# arduino_board_rev_1_3.net
KiCad netlist of a schematic drawn in EAGLE
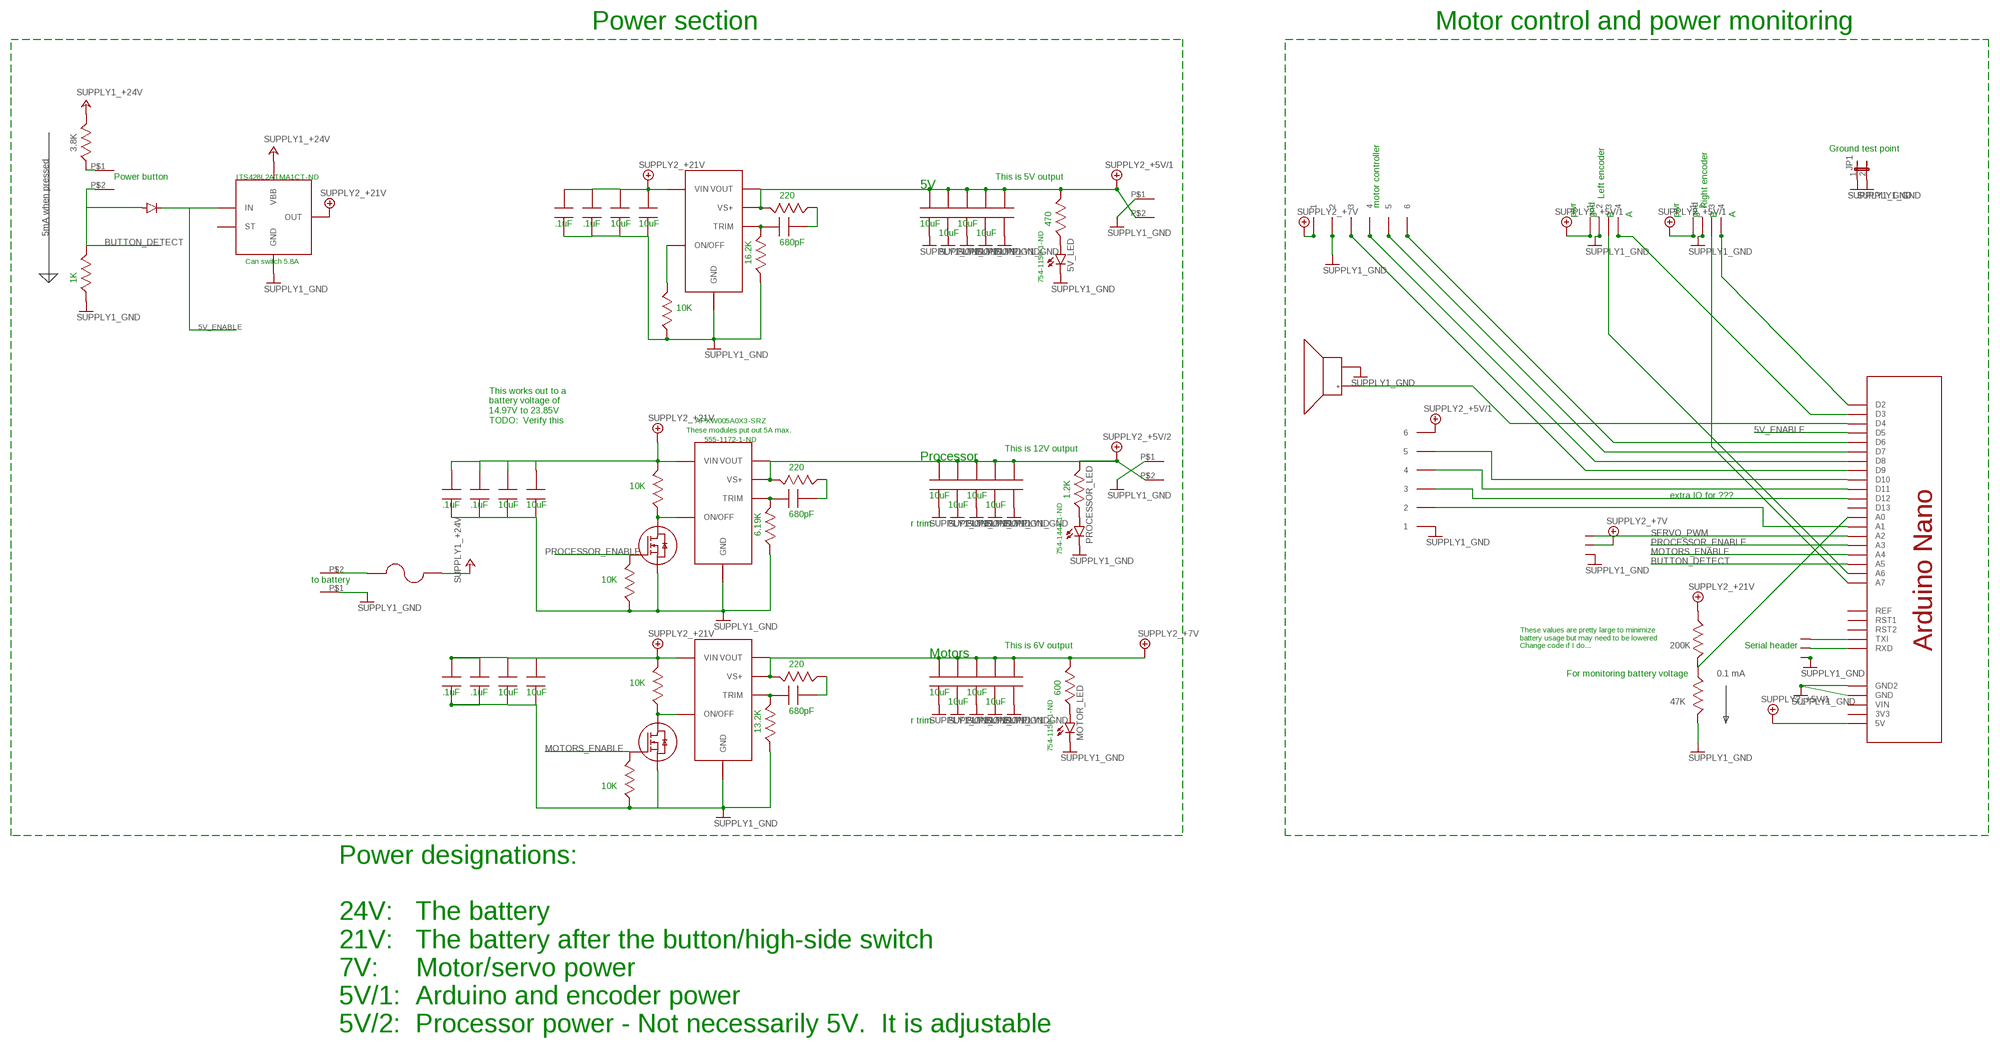
[diagram p0: schematic, sheet 1]

(export (version "E")
  (design (tool "Eeschema 10.0.6"))
  (components
    (comp (ref "5V_C_680PF")
      (value "JACK_CAPACITOR0805")
      (footprint "eagle-import:JACK_0805")
      (libsource (lib "eagle-import") (part "JACK_CAPACITOR0805"))
    )
    (comp (ref "5V_IN_CAP_1")
      (value "JACK_CAPACITOR")
      (footprint "eagle-import:JACK_1210")
      (libsource (lib "eagle-import") (part "JACK_CAPACITOR"))
    )
    (comp (ref "5V_IN_CAP_2")
      (value "JACK_CAPACITOR")
      (footprint "eagle-import:JACK_1210")
      (libsource (lib "eagle-import") (part "JACK_CAPACITOR"))
    )
    (comp (ref "5V_IN_CAP_3")
      (value "JACK_CAPACITOR")
      (footprint "eagle-import:JACK_1210")
      (libsource (lib "eagle-import") (part "JACK_CAPACITOR"))
    )
    (comp (ref "5V_IN_CAP_4")
      (value "JACK_CAPACITOR")
      (footprint "eagle-import:JACK_1210")
      (libsource (lib "eagle-import") (part "JACK_CAPACITOR"))
    )
    (comp (ref "5V_LED")
      (value "LED_LEDSML1206")
      (footprint "eagle-import:LED_SML1206")
      (libsource (lib "eagle-import") (part "LED_LEDSML1206"))
    )
    (comp (ref "5V_LED_R1")
      (value "JACK_RESISTOR0805")
      (footprint "eagle-import:JACK_0805")
      (libsource (lib "eagle-import") (part "JACK_RESISTOR0805"))
    )
    (comp (ref "5V_OUT_CAP_1")
      (value "JACK_CAPACITOR")
      (footprint "eagle-import:JACK_1210")
      (libsource (lib "eagle-import") (part "JACK_CAPACITOR"))
    )
    (comp (ref "5V_OUT_CAP_2")
      (value "JACK_CAPACITOR")
      (footprint "eagle-import:JACK_1210")
      (libsource (lib "eagle-import") (part "JACK_CAPACITOR"))
    )
    (comp (ref "5V_OUT_CAP_3")
      (value "JACK_CAPACITOR")
      (footprint "eagle-import:JACK_1210")
      (libsource (lib "eagle-import") (part "JACK_CAPACITOR"))
    )
    (comp (ref "5V_OUT_CAP_4")
      (value "JACK_CAPACITOR")
      (footprint "eagle-import:JACK_1210")
      (libsource (lib "eagle-import") (part "JACK_CAPACITOR"))
    )
    (comp (ref "5V_OUT_CAP_5")
      (value "JACK_CAPACITOR")
      (footprint "eagle-import:JACK_1210")
      (libsource (lib "eagle-import") (part "JACK_CAPACITOR"))
    )
    (comp (ref "5V_REGULATOR_PULLDOWN")
      (value "JACK_RESISTOR0805")
      (footprint "eagle-import:JACK_0805")
      (libsource (lib "eagle-import") (part "JACK_RESISTOR0805"))
    )
    (comp (ref "5V_R_220")
      (value "JACK_RESISTOR0805")
      (footprint "eagle-import:JACK_0805")
      (libsource (lib "eagle-import") (part "JACK_RESISTOR0805"))
    )
    (comp (ref "BATTERY_VOLTAGE_DIVIDER_HIGH")
      (value "JACK_RESISTOR0805")
      (footprint "eagle-import:JACK_0805")
      (libsource (lib "eagle-import") (part "JACK_RESISTOR0805"))
    )
    (comp (ref "BATTERY_VOLTAGE_DIVIDER_LOW")
      (value "JACK_RESISTOR0805")
      (footprint "eagle-import:JACK_0805")
      (libsource (lib "eagle-import") (part "JACK_RESISTOR0805"))
    )
    (comp (ref "BEEPER")
      (value "JACK_BEEPER")
      (footprint "eagle-import:JACK_BEEPER_433-1033-ND")
      (libsource (lib "eagle-import") (part "JACK_BEEPER"))
    )
    (comp (ref "DC2DC_PROCESSOR_")
      (value "JACK_DC_TO_DC_VARIABLE_555-1172-1-ND")
      (footprint "eagle-import:JACK_DC2DC_555-1172-1-ND")
      (libsource (lib "eagle-import") (part "JACK_DC_TO_DC_VARIABLE_555-1172-1-ND"))
    )
    (comp (ref "HIGH-SIDE_BLOCKING_DIODE")
      (value "JACK_DIODESOD-23/SC-76")
      (footprint "eagle-import:JACK_SOD-323_SC-76")
      (libsource (lib "eagle-import") (part "JACK_DIODESOD-23/SC-76"))
    )
    (comp (ref "HIGH-SIDE_BUTTON_DIVIDER_HIGH")
      (value "JACK_RESISTOR0805")
      (footprint "eagle-import:JACK_0805")
      (libsource (lib "eagle-import") (part "JACK_RESISTOR0805"))
    )
    (comp (ref "HIGH-SIDE_SWITCH")
      (value "JACK_HIGH-SIDE_SWITCH_INFINEON_ITS428L2")
      (footprint "eagle-import:JACK_INFINEON_TO-252-5-11")
      (libsource (lib "eagle-import") (part "JACK_HIGH-SIDE_SWITCH_INFINEON_ITS428L2"))
    )
    (comp (ref "HIGH-SIDE_SWITCH_BUTTON_DIVIDER_LOW")
      (value "JACK_RESISTOR0805")
      (footprint "eagle-import:JACK_0805")
      (libsource (lib "eagle-import") (part "JACK_RESISTOR0805"))
    )
    (comp (ref "JP1")
      (value "JUMPER_JP1E")
      (footprint "eagle-import:JUMPER_JP1")
      (libsource (lib "eagle-import") (part "JUMPER_JP1E"))
    )
    (comp (ref "MOTOR.1UF")
      (value "JACK_CAPACITOR")
      (footprint "eagle-import:JACK_1210")
      (libsource (lib "eagle-import") (part "JACK_CAPACITOR"))
    )
    (comp (ref "MOTOR_C_680PF")
      (value "JACK_CAPACITOR0805")
      (footprint "eagle-import:JACK_0805")
      (libsource (lib "eagle-import") (part "JACK_CAPACITOR0805"))
    )
    (comp (ref "MOTOR_ENABLE_MOSFET")
      (value "JACK_MOSFET_N_CHANNELBSS138LCT-ND")
      (footprint "eagle-import:JACK_SOT23")
      (libsource (lib "eagle-import") (part "JACK_MOSFET_N_CHANNELBSS138LCT-ND"))
    )
    (comp (ref "MOTOR_IN.1UF")
      (value "JACK_CAPACITOR")
      (footprint "eagle-import:JACK_1210")
      (libsource (lib "eagle-import") (part "JACK_CAPACITOR"))
    )
    (comp (ref "MOTOR_IN.1UF1")
      (value "JACK_CAPACITOR")
      (footprint "eagle-import:JACK_1210")
      (libsource (lib "eagle-import") (part "JACK_CAPACITOR"))
    )
    (comp (ref "MOTOR_IN.1UF4")
      (value "JACK_CAPACITOR")
      (footprint "eagle-import:JACK_1210")
      (libsource (lib "eagle-import") (part "JACK_CAPACITOR"))
    )
    (comp (ref "MOTOR_IN10UF")
      (value "JACK_CAPACITOR")
      (footprint "eagle-import:JACK_1210")
      (libsource (lib "eagle-import") (part "JACK_CAPACITOR"))
    )
    (comp (ref "MOTOR_LED")
      (value "LED_LEDSML1206")
      (footprint "eagle-import:LED_SML1206")
      (libsource (lib "eagle-import") (part "LED_LEDSML1206"))
    )
    (comp (ref "MOTOR_LED_R")
      (value "JACK_RESISTOR0805")
      (footprint "eagle-import:JACK_0805")
      (libsource (lib "eagle-import") (part "JACK_RESISTOR0805"))
    )
    (comp (ref "MOTOR_MOSFET_PULLDOWN")
      (value "JACK_RESISTOR0805")
      (footprint "eagle-import:JACK_0805")
      (libsource (lib "eagle-import") (part "JACK_RESISTOR0805"))
    )
    (comp (ref "MOTOR_PULLUP")
      (value "JACK_RESISTOR0805")
      (footprint "eagle-import:JACK_0805")
      (libsource (lib "eagle-import") (part "JACK_RESISTOR0805"))
    )
    (comp (ref "MOTOR_R_220")
      (value "JACK_RESISTOR0805")
      (footprint "eagle-import:JACK_0805")
      (libsource (lib "eagle-import") (part "JACK_RESISTOR0805"))
    )
    (comp (ref "MOTOR_TRIM")
      (value "JACK_RESISTOR0805")
      (footprint "eagle-import:JACK_0805")
      (libsource (lib "eagle-import") (part "JACK_RESISTOR0805"))
    )
    (comp (ref "MOTOTR10UF")
      (value "JACK_CAPACITOR")
      (footprint "eagle-import:JACK_1210")
      (libsource (lib "eagle-import") (part "JACK_CAPACITOR"))
    )
    (comp (ref "MOTOTR10UF1")
      (value "JACK_CAPACITOR")
      (footprint "eagle-import:JACK_1210")
      (libsource (lib "eagle-import") (part "JACK_CAPACITOR"))
    )
    (comp (ref "MOTOTR10UF2")
      (value "JACK_CAPACITOR")
      (footprint "eagle-import:JACK_1210")
      (libsource (lib "eagle-import") (part "JACK_CAPACITOR"))
    )
    (comp (ref "MOTOTR10UF3")
      (value "JACK_CAPACITOR")
      (footprint "eagle-import:JACK_1210")
      (libsource (lib "eagle-import") (part "JACK_CAPACITOR"))
    )
    (comp (ref "PROC.1UF")
      (value "JACK_CAPACITOR")
      (footprint "eagle-import:JACK_1210")
      (libsource (lib "eagle-import") (part "JACK_CAPACITOR"))
    )
    (comp (ref "PROC10UF")
      (value "JACK_CAPACITOR")
      (footprint "eagle-import:JACK_1210")
      (libsource (lib "eagle-import") (part "JACK_CAPACITOR"))
    )
    (comp (ref "PROC10UF1")
      (value "JACK_CAPACITOR")
      (footprint "eagle-import:JACK_1210")
      (libsource (lib "eagle-import") (part "JACK_CAPACITOR"))
    )
    (comp (ref "PROC10UF2")
      (value "JACK_CAPACITOR")
      (footprint "eagle-import:JACK_1210")
      (libsource (lib "eagle-import") (part "JACK_CAPACITOR"))
    )
    (comp (ref "PROC10UF3")
      (value "JACK_CAPACITOR")
      (footprint "eagle-import:JACK_1210")
      (libsource (lib "eagle-import") (part "JACK_CAPACITOR"))
    )
    (comp (ref "PROCESSOR_C_680PF")
      (value "JACK_CAPACITOR0805")
      (footprint "eagle-import:JACK_0805")
      (libsource (lib "eagle-import") (part "JACK_CAPACITOR0805"))
    )
    (comp (ref "PROCESSOR_ENABLE_MOSFET")
      (value "JACK_MOSFET_N_CHANNELBSS138LCT-ND")
      (footprint "eagle-import:JACK_SOT23")
      (libsource (lib "eagle-import") (part "JACK_MOSFET_N_CHANNELBSS138LCT-ND"))
    )
    (comp (ref "PROCESSOR_LED")
      (value "LED_LEDSML1206")
      (footprint "eagle-import:LED_SML1206")
      (libsource (lib "eagle-import") (part "LED_LEDSML1206"))
    )
    (comp (ref "PROCESSOR_LED_R")
      (value "JACK_RESISTOR0805")
      (footprint "eagle-import:JACK_0805")
      (libsource (lib "eagle-import") (part "JACK_RESISTOR0805"))
    )
    (comp (ref "PROCESSOR_MOSFET_PULLDOWN")
      (value "JACK_RESISTOR0805")
      (footprint "eagle-import:JACK_0805")
      (libsource (lib "eagle-import") (part "JACK_RESISTOR0805"))
    )
    (comp (ref "PROCESSOR_PULLUP")
      (value "JACK_RESISTOR0805")
      (footprint "eagle-import:JACK_0805")
      (libsource (lib "eagle-import") (part "JACK_RESISTOR0805"))
    )
    (comp (ref "PROCESSOR_R_220")
      (value "JACK_RESISTOR0805")
      (footprint "eagle-import:JACK_0805")
      (libsource (lib "eagle-import") (part "JACK_RESISTOR0805"))
    )
    (comp (ref "PROC_IN10UF")
      (value "JACK_CAPACITOR")
      (footprint "eagle-import:JACK_1210")
      (libsource (lib "eagle-import") (part "JACK_CAPACITOR"))
    )
    (comp (ref "PROC_IN_.1UF")
      (value "JACK_CAPACITOR")
      (footprint "eagle-import:JACK_1210")
      (libsource (lib "eagle-import") (part "JACK_CAPACITOR"))
    )
    (comp (ref "PROC_IN_.1UF1")
      (value "JACK_CAPACITOR")
      (footprint "eagle-import:JACK_1210")
      (libsource (lib "eagle-import") (part "JACK_CAPACITOR"))
    )
    (comp (ref "PROC_IN_.1UF2")
      (value "JACK_CAPACITOR")
      (footprint "eagle-import:JACK_1210")
      (libsource (lib "eagle-import") (part "JACK_CAPACITOR"))
    )
    (comp (ref "RTRIM_5V")
      (value "JACK_RESISTOR0805")
      (footprint "eagle-import:JACK_0805")
      (libsource (lib "eagle-import") (part "JACK_RESISTOR0805"))
    )
    (comp (ref "RTRIM_PROCESSOR")
      (value "JACK_RESISTOR0805")
      (footprint "eagle-import:JACK_0805")
      (libsource (lib "eagle-import") (part "JACK_RESISTOR0805"))
    )
    (comp (ref "SERVO_HEADER")
      (value "JACK_CONNECTOR_3_PIN")
      (footprint "eagle-import:JACK_THREE_.1__HOLES")
      (libsource (lib "eagle-import") (part "JACK_CONNECTOR_3_PIN"))
    )
    (comp (ref "U$1")
      (value "JACK_SCREW_TERMINAL_2_CONDUCTORAMP-282837-2")
      (footprint "eagle-import:JACK_AMP-282837-2")
      (libsource (lib "eagle-import") (part "JACK_SCREW_TERMINAL_2_CONDUCTORAMP-282837-2"))
    )
    (comp (ref "U$2")
      (value "JACK_SCREW_TERMINAL_2_CONDUCTORAMP-282837-2")
      (footprint "eagle-import:JACK_AMP-282837-2")
      (libsource (lib "eagle-import") (part "JACK_SCREW_TERMINAL_2_CONDUCTORAMP-282837-2"))
    )
    (comp (ref "U$3")
      (value "JACK_CONNECTOR_6_PINJST_MAYBE")
      (footprint "eagle-import:JACK_JST_6_PIN_.1_")
      (libsource (lib "eagle-import") (part "JACK_CONNECTOR_6_PINJST_MAYBE"))
    )
    (comp (ref "U$4")
      (value "JACK_DC_TO_DC_VARIABLE_555-1172-1-ND")
      (footprint "eagle-import:JACK_DC2DC_555-1172-1-ND")
      (libsource (lib "eagle-import") (part "JACK_DC_TO_DC_VARIABLE_555-1172-1-ND"))
    )
    (comp (ref "U$5")
      (value "JACK_SCREW_TERMINAL_2_CONDUCTORAMP-282837-2")
      (footprint "eagle-import:JACK_AMP-282837-2")
      (libsource (lib "eagle-import") (part "JACK_SCREW_TERMINAL_2_CONDUCTORAMP-282837-2"))
    )
    (comp (ref "U$6")
      (value "JACK_SCREW_TERMINAL_2_CONDUCTORAMP-282837-2")
      (footprint "eagle-import:JACK_AMP-282837-2")
      (libsource (lib "eagle-import") (part "JACK_SCREW_TERMINAL_2_CONDUCTORAMP-282837-2"))
    )
    (comp (ref "U$9")
      (value "JACK_CONNECTOR_6_PINJST_MAYBE")
      (footprint "eagle-import:JACK_JST_6_PIN_.1_")
      (libsource (lib "eagle-import") (part "JACK_CONNECTOR_6_PINJST_MAYBE"))
    )
    (comp (ref "U$10")
      (value "JACK_CONNECTOR_4_PIN")
      (footprint "eagle-import:JACK_JST_4_PIN_.1_")
      (libsource (lib "eagle-import") (part "JACK_CONNECTOR_4_PIN"))
    )
    (comp (ref "U$11")
      (value "JACK_FUSE_HOLDER_F065-ND")
      (footprint "eagle-import:JACK_FUSE_HOLDER_F064-ND")
      (libsource (lib "eagle-import") (part "JACK_FUSE_HOLDER_F065-ND"))
    )
    (comp (ref "U$12")
      (value "JACK_CONNECTOR_4_PIN")
      (footprint "eagle-import:JACK_JST_4_PIN_.1_")
      (libsource (lib "eagle-import") (part "JACK_CONNECTOR_4_PIN"))
    )
    (comp (ref "U$13")
      (value "JACK_CONNECTOR_3_PINMAYBE_JST")
      (footprint "eagle-import:JACK_JST_3_PIN_.1_")
      (libsource (lib "eagle-import") (part "JACK_CONNECTOR_3_PINMAYBE_JST"))
    )
    (comp (ref "U$14")
      (value "JACK_ARDUINO_NANO")
      (footprint "eagle-import:JACK_ARDUINO_NANO")
      (libsource (lib "eagle-import") (part "JACK_ARDUINO_NANO"))
    )
    (comp (ref "U$17")
      (value "JACK_DC_TO_DC_VARIABLE_555-1172-1-ND")
      (footprint "eagle-import:JACK_DC2DC_555-1172-1-ND")
      (libsource (lib "eagle-import") (part "JACK_DC_TO_DC_VARIABLE_555-1172-1-ND"))
    )
  )
  (nets
    (net (code "1") (name "/5V_ENABLE") (class "Default")
      (node (ref "HIGH-SIDE_BLOCKING_DIODE") (pin "C") (pinfunction "C_C") (pintype "bidirectional"))
      (node (ref "HIGH-SIDE_SWITCH") (pin "2") (pinfunction "IN_2") (pintype "bidirectional"))
      (node (ref "U$14") (pin "P$8") (pinfunction "D5_P$8") (pintype "bidirectional"))
    )
    (net (code "2") (name "/BUTTON_DETECT") (class "Default")
      (node (ref "HIGH-SIDE_BLOCKING_DIODE") (pin "A") (pinfunction "A_A") (pintype "bidirectional"))
      (node (ref "HIGH-SIDE_SWITCH_BUTTON_DIVIDER_LOW") (pin "P$3") (pinfunction "P$3_P$3") (pintype "bidirectional"))
      (node (ref "U$1") (pin "P$2") (pinfunction "P$2_P$2") (pintype "bidirectional"))
      (node (ref "U$14") (pin "P$22") (pinfunction "A5_P$22") (pintype "bidirectional"))
    )
    (net (code "3") (name "/MOTORS_ENABLE") (class "Default")
      (node (ref "MOTOR_ENABLE_MOSFET") (pin "1") (pinfunction "G_1") (pintype "bidirectional"))
      (node (ref "MOTOR_MOSFET_PULLDOWN") (pin "P$3") (pinfunction "P$3_P$3") (pintype "bidirectional"))
      (node (ref "U$14") (pin "P$23") (pinfunction "A4_P$23") (pintype "bidirectional"))
    )
    (net (code "4") (name "/PROCESSOR_ENABLE") (class "Default")
      (node (ref "PROCESSOR_ENABLE_MOSFET") (pin "1") (pinfunction "G_1") (pintype "bidirectional"))
      (node (ref "PROCESSOR_MOSFET_PULLDOWN") (pin "P$3") (pinfunction "P$3_P$3") (pintype "bidirectional"))
      (node (ref "U$14") (pin "P$24") (pinfunction "A3_P$24") (pintype "bidirectional"))
    )
    (net (code "5") (name "/SERVO_PWM") (class "Default")
      (node (ref "SERVO_HEADER") (pin "3") (pinfunction "3_3") (pintype "bidirectional"))
      (node (ref "U$14") (pin "P$25") (pinfunction "A2_P$25") (pintype "bidirectional"))
    )
    (net (code "6") (name "Net-(5V_C_680PF-1)") (class "Default")
      (node (ref "5V_C_680PF") (pin "P$2") (pinfunction "1_P$2") (pintype "bidirectional"))
      (node (ref "5V_R_220") (pin "P$2") (pinfunction "P$2_P$2") (pintype "bidirectional"))
    )
    (net (code "7") (name "Net-(5V_C_680PF-2)") (class "Default")
      (node (ref "5V_C_680PF") (pin "P$3") (pinfunction "2_P$3") (pintype "bidirectional"))
      (node (ref "RTRIM_5V") (pin "P$3") (pinfunction "P$3_P$3") (pintype "bidirectional"))
      (node (ref "U$4") (pin "TRIM") (pinfunction "TRIM_TRIM") (pintype "bidirectional"))
    )
    (net (code "8") (name "Net-(5V_LED-PadA)") (class "Default")
      (node (ref "5V_LED") (pin "A") (pinfunction "A_A") (pintype "passive"))
      (node (ref "5V_LED_R1") (pin "P$2") (pinfunction "P$2_P$2") (pintype "bidirectional"))
    )
    (net (code "9") (name "Net-(5V_REGULATOR_PULLDOWN-PadP$3)") (class "Default")
      (node (ref "5V_REGULATOR_PULLDOWN") (pin "P$3") (pinfunction "P$3_P$3") (pintype "bidirectional"))
      (node (ref "U$4") (pin "ON/OFF") (pinfunction "ON/OFF_ON/OFF") (pintype "bidirectional"))
    )
    (net (code "10") (name "Net-(HIGH-SIDE_BUTTON_DIVIDER_HIGH-PadP$2)") (class "Default")
      (node (ref "HIGH-SIDE_BUTTON_DIVIDER_HIGH") (pin "P$2") (pinfunction "P$2_P$2") (pintype "bidirectional"))
      (node (ref "U$1") (pin "P$1") (pinfunction "P$1_P$1") (pintype "bidirectional"))
    )
    (net (code "11") (name "Net-(MOTOR_C_680PF-1)") (class "Default")
      (node (ref "MOTOR_C_680PF") (pin "P$2") (pinfunction "1_P$2") (pintype "bidirectional"))
      (node (ref "MOTOR_R_220") (pin "P$2") (pinfunction "P$2_P$2") (pintype "bidirectional"))
    )
    (net (code "12") (name "Net-(MOTOR_C_680PF-2)") (class "Default")
      (node (ref "MOTOR_C_680PF") (pin "P$3") (pinfunction "2_P$3") (pintype "bidirectional"))
      (node (ref "MOTOR_TRIM") (pin "P$3") (pinfunction "P$3_P$3") (pintype "bidirectional"))
      (node (ref "U$17") (pin "TRIM") (pinfunction "TRIM_TRIM") (pintype "bidirectional"))
    )
    (net (code "13") (name "Net-(MOTOR_ENABLE_MOSFET-D)") (class "Default")
      (node (ref "MOTOR_ENABLE_MOSFET") (pin "3") (pinfunction "D_3") (pintype "bidirectional"))
      (node (ref "MOTOR_PULLUP") (pin "P$2") (pinfunction "P$2_P$2") (pintype "bidirectional"))
      (node (ref "U$17") (pin "ON/OFF") (pinfunction "ON/OFF_ON/OFF") (pintype "bidirectional"))
    )
    (net (code "14") (name "Net-(MOTOR_LED-PadA)") (class "Default")
      (node (ref "MOTOR_LED") (pin "A") (pinfunction "A_A") (pintype "passive"))
      (node (ref "MOTOR_LED_R") (pin "P$2") (pinfunction "P$2_P$2") (pintype "bidirectional"))
    )
    (net (code "15") (name "Net-(PROCESSOR_C_680PF-1)") (class "Default")
      (node (ref "PROCESSOR_C_680PF") (pin "P$2") (pinfunction "1_P$2") (pintype "bidirectional"))
      (node (ref "PROCESSOR_R_220") (pin "P$2") (pinfunction "P$2_P$2") (pintype "bidirectional"))
    )
    (net (code "16") (name "Net-(PROCESSOR_C_680PF-2)") (class "Default")
      (node (ref "DC2DC_PROCESSOR_") (pin "TRIM") (pinfunction "TRIM_TRIM") (pintype "bidirectional"))
      (node (ref "PROCESSOR_C_680PF") (pin "P$3") (pinfunction "2_P$3") (pintype "bidirectional"))
      (node (ref "RTRIM_PROCESSOR") (pin "P$3") (pinfunction "P$3_P$3") (pintype "bidirectional"))
    )
    (net (code "17") (name "Net-(PROCESSOR_ENABLE_MOSFET-D)") (class "Default")
      (node (ref "DC2DC_PROCESSOR_") (pin "ON/OFF") (pinfunction "ON/OFF_ON/OFF") (pintype "bidirectional"))
      (node (ref "PROCESSOR_ENABLE_MOSFET") (pin "3") (pinfunction "D_3") (pintype "bidirectional"))
      (node (ref "PROCESSOR_PULLUP") (pin "P$2") (pinfunction "P$2_P$2") (pintype "bidirectional"))
    )
    (net (code "18") (name "Net-(PROCESSOR_LED-PadA)") (class "Default")
      (node (ref "PROCESSOR_LED") (pin "A") (pinfunction "A_A") (pintype "passive"))
      (node (ref "PROCESSOR_LED_R") (pin "P$2") (pinfunction "P$2_P$2") (pintype "bidirectional"))
    )
    (net (code "19") (name "Net-(U$11-PadP$2)") (class "Default")
      (node (ref "U$11") (pin "P$2") (pinfunction "P$2_P$2") (pintype "bidirectional"))
      (node (ref "U$6") (pin "P$2") (pinfunction "P$2_P$2") (pintype "bidirectional"))
    )
    (net (code "20") (name "Net-(U$14-A0)") (class "Default")
      (node (ref "BATTERY_VOLTAGE_DIVIDER_HIGH") (pin "P$3") (pinfunction "P$3_P$3") (pintype "bidirectional"))
      (node (ref "BATTERY_VOLTAGE_DIVIDER_LOW") (pin "P$2") (pinfunction "P$2_P$2") (pintype "bidirectional"))
      (node (ref "U$14") (pin "P$27") (pinfunction "A0_P$27") (pintype "bidirectional"))
    )
    (net (code "21") (name "Net-(U$14-A1)") (class "Default")
      (node (ref "U$14") (pin "P$26") (pinfunction "A1_P$26") (pintype "bidirectional"))
      (node (ref "U$3") (pin "2") (pinfunction "2_2") (pintype "bidirectional"))
    )
    (net (code "22") (name "Net-(U$14-A6)") (class "Default")
      (node (ref "U$10") (pin "3") (pinfunction "3_3") (pintype "bidirectional"))
      (node (ref "U$14") (pin "P$21") (pinfunction "A6_P$21") (pintype "bidirectional"))
    )
    (net (code "23") (name "Net-(U$14-A7)") (class "Default")
      (node (ref "U$12") (pin "3") (pinfunction "3_3") (pintype "bidirectional"))
      (node (ref "U$14") (pin "P$20") (pinfunction "A7_P$20") (pintype "bidirectional"))
    )
    (net (code "24") (name "Net-(U$14-D2)") (class "Default")
      (node (ref "U$12") (pin "4") (pinfunction "4_4") (pintype "bidirectional"))
      (node (ref "U$14") (pin "P$11") (pinfunction "D2_P$11") (pintype "bidirectional"))
    )
    (net (code "25") (name "Net-(U$14-D3)") (class "Default")
      (node (ref "U$10") (pin "4") (pinfunction "4_4") (pintype "bidirectional"))
      (node (ref "U$14") (pin "P$10") (pinfunction "D3_P$10") (pintype "bidirectional"))
    )
    (net (code "26") (name "Net-(U$14-D4)") (class "Default")
      (node (ref "BEEPER") (pin "+") (pinfunction "+_+") (pintype "bidirectional"))
      (node (ref "U$14") (pin "P$9") (pinfunction "D4_P$9") (pintype "bidirectional"))
    )
    (net (code "27") (name "Net-(U$14-D6)") (class "Default")
      (node (ref "U$14") (pin "P$7") (pinfunction "D6_P$7") (pintype "bidirectional"))
      (node (ref "U$9") (pin "6") (pinfunction "6_6") (pintype "bidirectional"))
    )
    (net (code "28") (name "Net-(U$14-D7)") (class "Default")
      (node (ref "U$14") (pin "P$6") (pinfunction "D7_P$6") (pintype "bidirectional"))
      (node (ref "U$9") (pin "5") (pinfunction "5_5") (pintype "bidirectional"))
    )
    (net (code "29") (name "Net-(U$14-D8)") (class "Default")
      (node (ref "U$14") (pin "P$5") (pinfunction "D8_P$5") (pintype "bidirectional"))
      (node (ref "U$9") (pin "4") (pinfunction "4_4") (pintype "bidirectional"))
    )
    (net (code "30") (name "Net-(U$14-D9)") (class "Default")
      (node (ref "U$14") (pin "P$4") (pinfunction "D9_P$4") (pintype "bidirectional"))
      (node (ref "U$9") (pin "3") (pinfunction "3_3") (pintype "bidirectional"))
    )
    (net (code "31") (name "Net-(U$14-D10)") (class "Default")
      (node (ref "U$14") (pin "P$3") (pinfunction "D10_P$3") (pintype "bidirectional"))
      (node (ref "U$3") (pin "5") (pinfunction "5_5") (pintype "bidirectional"))
    )
    (net (code "32") (name "Net-(U$14-D11)") (class "Default")
      (node (ref "U$14") (pin "P$2") (pinfunction "D11_P$2") (pintype "bidirectional"))
      (node (ref "U$3") (pin "4") (pinfunction "4_4") (pintype "bidirectional"))
    )
    (net (code "33") (name "Net-(U$14-D12)") (class "Default")
      (node (ref "U$14") (pin "P$1") (pinfunction "D12_P$1") (pintype "bidirectional"))
      (node (ref "U$3") (pin "3") (pinfunction "3_3") (pintype "bidirectional"))
    )
    (net (code "34") (name "Net-(U$14-RXD)") (class "Default")
      (node (ref "U$13") (pin "2") (pinfunction "2_2") (pintype "bidirectional"))
      (node (ref "U$14") (pin "P$14") (pinfunction "RXD_P$14") (pintype "bidirectional"))
    )
    (net (code "35") (name "Net-(U$14-TXI)") (class "Default")
      (node (ref "U$13") (pin "3") (pinfunction "3_3") (pintype "bidirectional"))
      (node (ref "U$14") (pin "P$15") (pinfunction "TXI_P$15") (pintype "bidirectional"))
    )
    (net (code "36") (name "SUPPLY1_+24V") (class "Default")
      (node (ref "HIGH-SIDE_BUTTON_DIVIDER_HIGH") (pin "P$3") (pinfunction "P$3_P$3") (pintype "bidirectional"))
      (node (ref "HIGH-SIDE_SWITCH") (pin "TAB") (pinfunction "VBB_TAB") (pintype "bidirectional"))
      (node (ref "U$11") (pin "P$1") (pinfunction "P$1_P$1") (pintype "bidirectional"))
    )
    (net (code "37") (name "SUPPLY1_GND") (class "Default")
      (node (ref "5V_IN_CAP_1") (pin "1") (pinfunction "1_1") (pintype "bidirectional"))
      (node (ref "5V_IN_CAP_2") (pin "1") (pinfunction "1_1") (pintype "bidirectional"))
      (node (ref "5V_IN_CAP_3") (pin "1") (pinfunction "1_1") (pintype "bidirectional"))
      (node (ref "5V_IN_CAP_4") (pin "1") (pinfunction "1_1") (pintype "bidirectional"))
      (node (ref "5V_LED") (pin "C") (pinfunction "C_C") (pintype "passive"))
      (node (ref "5V_OUT_CAP_1") (pin "1") (pinfunction "1_1") (pintype "bidirectional"))
      (node (ref "5V_OUT_CAP_2") (pin "1") (pinfunction "1_1") (pintype "bidirectional"))
      (node (ref "5V_OUT_CAP_3") (pin "1") (pinfunction "1_1") (pintype "bidirectional"))
      (node (ref "5V_OUT_CAP_4") (pin "1") (pinfunction "1_1") (pintype "bidirectional"))
      (node (ref "5V_OUT_CAP_5") (pin "1") (pinfunction "1_1") (pintype "bidirectional"))
      (node (ref "5V_REGULATOR_PULLDOWN") (pin "P$2") (pinfunction "P$2_P$2") (pintype "bidirectional"))
      (node (ref "BATTERY_VOLTAGE_DIVIDER_LOW") (pin "P$3") (pinfunction "P$3_P$3") (pintype "bidirectional"))
      (node (ref "BEEPER") (pin "-") (pinfunction "-_-") (pintype "bidirectional"))
      (node (ref "DC2DC_PROCESSOR_") (pin "GND") (pinfunction "GND_GND") (pintype "bidirectional"))
      (node (ref "HIGH-SIDE_SWITCH") (pin "1") (pinfunction "GND_1") (pintype "bidirectional"))
      (node (ref "HIGH-SIDE_SWITCH_BUTTON_DIVIDER_LOW") (pin "P$2") (pinfunction "P$2_P$2") (pintype "bidirectional"))
      (node (ref "JP1") (pin "1") (pinfunction "1_1") (pintype "passive"))
      (node (ref "JP1") (pin "2") (pinfunction "2_2") (pintype "passive"))
      (node (ref "MOTOR.1UF") (pin "1") (pinfunction "1_1") (pintype "bidirectional"))
      (node (ref "MOTOR_ENABLE_MOSFET") (pin "2") (pinfunction "S_2") (pintype "bidirectional"))
      (node (ref "MOTOR_IN.1UF") (pin "1") (pinfunction "1_1") (pintype "bidirectional"))
      (node (ref "MOTOR_IN.1UF1") (pin "1") (pinfunction "1_1") (pintype "bidirectional"))
      (node (ref "MOTOR_IN.1UF4") (pin "1") (pinfunction "1_1") (pintype "bidirectional"))
      (node (ref "MOTOR_IN10UF") (pin "1") (pinfunction "1_1") (pintype "bidirectional"))
      (node (ref "MOTOR_LED") (pin "C") (pinfunction "C_C") (pintype "passive"))
      (node (ref "MOTOR_MOSFET_PULLDOWN") (pin "P$2") (pinfunction "P$2_P$2") (pintype "bidirectional"))
      (node (ref "MOTOR_TRIM") (pin "P$2") (pinfunction "P$2_P$2") (pintype "bidirectional"))
      (node (ref "MOTOTR10UF") (pin "1") (pinfunction "1_1") (pintype "bidirectional"))
      (node (ref "MOTOTR10UF1") (pin "1") (pinfunction "1_1") (pintype "bidirectional"))
      (node (ref "MOTOTR10UF2") (pin "1") (pinfunction "1_1") (pintype "bidirectional"))
      (node (ref "MOTOTR10UF3") (pin "1") (pinfunction "1_1") (pintype "bidirectional"))
      (node (ref "PROC.1UF") (pin "1") (pinfunction "1_1") (pintype "bidirectional"))
      (node (ref "PROC10UF") (pin "1") (pinfunction "1_1") (pintype "bidirectional"))
      (node (ref "PROC10UF1") (pin "1") (pinfunction "1_1") (pintype "bidirectional"))
      (node (ref "PROC10UF2") (pin "1") (pinfunction "1_1") (pintype "bidirectional"))
      (node (ref "PROC10UF3") (pin "1") (pinfunction "1_1") (pintype "bidirectional"))
      (node (ref "PROCESSOR_ENABLE_MOSFET") (pin "2") (pinfunction "S_2") (pintype "bidirectional"))
      (node (ref "PROCESSOR_LED") (pin "C") (pinfunction "C_C") (pintype "passive"))
      (node (ref "PROCESSOR_MOSFET_PULLDOWN") (pin "P$2") (pinfunction "P$2_P$2") (pintype "bidirectional"))
      (node (ref "PROC_IN10UF") (pin "1") (pinfunction "1_1") (pintype "bidirectional"))
      (node (ref "PROC_IN_.1UF") (pin "1") (pinfunction "1_1") (pintype "bidirectional"))
      (node (ref "PROC_IN_.1UF1") (pin "1") (pinfunction "1_1") (pintype "bidirectional"))
      (node (ref "PROC_IN_.1UF2") (pin "1") (pinfunction "1_1") (pintype "bidirectional"))
      (node (ref "RTRIM_5V") (pin "P$2") (pinfunction "P$2_P$2") (pintype "bidirectional"))
      (node (ref "RTRIM_PROCESSOR") (pin "P$2") (pinfunction "P$2_P$2") (pintype "bidirectional"))
      (node (ref "SERVO_HEADER") (pin "1") (pinfunction "1_1") (pintype "bidirectional"))
      (node (ref "U$10") (pin "2") (pinfunction "2_2") (pintype "bidirectional"))
      (node (ref "U$12") (pin "2") (pinfunction "2_2") (pintype "bidirectional"))
      (node (ref "U$13") (pin "1") (pinfunction "1_1") (pintype "bidirectional"))
      (node (ref "U$14") (pin "P$12") (pinfunction "GND_P$12") (pintype "bidirectional"))
      (node (ref "U$14") (pin "P$17") (pinfunction "GND2_P$17") (pintype "bidirectional"))
      (node (ref "U$17") (pin "GND") (pinfunction "GND_GND") (pintype "bidirectional"))
      (node (ref "U$2") (pin "P$1") (pinfunction "P$1_P$1") (pintype "bidirectional"))
      (node (ref "U$3") (pin "1") (pinfunction "1_1") (pintype "bidirectional"))
      (node (ref "U$4") (pin "GND") (pinfunction "GND_GND") (pintype "bidirectional"))
      (node (ref "U$5") (pin "P$1") (pinfunction "P$1_P$1") (pintype "bidirectional"))
      (node (ref "U$6") (pin "P$1") (pinfunction "P$1_P$1") (pintype "bidirectional"))
      (node (ref "U$9") (pin "2") (pinfunction "2_2") (pintype "bidirectional"))
    )
    (net (code "38") (name "SUPPLY2_+5V{slash}1") (class "Default")
      (node (ref "5V_LED_R1") (pin "P$3") (pinfunction "P$3_P$3") (pintype "bidirectional"))
      (node (ref "5V_OUT_CAP_1") (pin "2") (pinfunction "2_2") (pintype "bidirectional"))
      (node (ref "5V_OUT_CAP_2") (pin "2") (pinfunction "2_2") (pintype "bidirectional"))
      (node (ref "5V_OUT_CAP_3") (pin "2") (pinfunction "2_2") (pintype "bidirectional"))
      (node (ref "5V_OUT_CAP_4") (pin "2") (pinfunction "2_2") (pintype "bidirectional"))
      (node (ref "5V_OUT_CAP_5") (pin "2") (pinfunction "2_2") (pintype "bidirectional"))
      (node (ref "5V_R_220") (pin "P$3") (pinfunction "P$3_P$3") (pintype "bidirectional"))
      (node (ref "U$10") (pin "1") (pinfunction "1_1") (pintype "bidirectional"))
      (node (ref "U$12") (pin "1") (pinfunction "1_1") (pintype "bidirectional"))
      (node (ref "U$14") (pin "P$19") (pinfunction "5V_P$19") (pintype "bidirectional"))
      (node (ref "U$2") (pin "P$2") (pinfunction "P$2_P$2") (pintype "bidirectional"))
      (node (ref "U$3") (pin "6") (pinfunction "6_6") (pintype "bidirectional"))
      (node (ref "U$4") (pin "VOUT") (pinfunction "VOUT_VOUT") (pintype "bidirectional"))
      (node (ref "U$4") (pin "VS+") (pinfunction "VS+_VS+") (pintype "bidirectional"))
    )
    (net (code "39") (name "SUPPLY2_+5V{slash}2") (class "Default")
      (node (ref "DC2DC_PROCESSOR_") (pin "VOUT") (pinfunction "VOUT_VOUT") (pintype "bidirectional"))
      (node (ref "DC2DC_PROCESSOR_") (pin "VS+") (pinfunction "VS+_VS+") (pintype "bidirectional"))
      (node (ref "PROC.1UF") (pin "2") (pinfunction "2_2") (pintype "bidirectional"))
      (node (ref "PROC10UF") (pin "2") (pinfunction "2_2") (pintype "bidirectional"))
      (node (ref "PROC10UF1") (pin "2") (pinfunction "2_2") (pintype "bidirectional"))
      (node (ref "PROC10UF2") (pin "2") (pinfunction "2_2") (pintype "bidirectional"))
      (node (ref "PROC10UF3") (pin "2") (pinfunction "2_2") (pintype "bidirectional"))
      (node (ref "PROCESSOR_LED_R") (pin "P$3") (pinfunction "P$3_P$3") (pintype "bidirectional"))
      (node (ref "PROCESSOR_R_220") (pin "P$3") (pinfunction "P$3_P$3") (pintype "bidirectional"))
      (node (ref "U$5") (pin "P$2") (pinfunction "P$2_P$2") (pintype "bidirectional"))
    )
    (net (code "40") (name "SUPPLY2_+7V") (class "Default")
      (node (ref "MOTOR.1UF") (pin "2") (pinfunction "2_2") (pintype "bidirectional"))
      (node (ref "MOTOR_LED_R") (pin "P$3") (pinfunction "P$3_P$3") (pintype "bidirectional"))
      (node (ref "MOTOR_R_220") (pin "P$3") (pinfunction "P$3_P$3") (pintype "bidirectional"))
      (node (ref "MOTOTR10UF") (pin "2") (pinfunction "2_2") (pintype "bidirectional"))
      (node (ref "MOTOTR10UF1") (pin "2") (pinfunction "2_2") (pintype "bidirectional"))
      (node (ref "MOTOTR10UF2") (pin "2") (pinfunction "2_2") (pintype "bidirectional"))
      (node (ref "MOTOTR10UF3") (pin "2") (pinfunction "2_2") (pintype "bidirectional"))
      (node (ref "SERVO_HEADER") (pin "2") (pinfunction "2_2") (pintype "bidirectional"))
      (node (ref "U$17") (pin "VOUT") (pinfunction "VOUT_VOUT") (pintype "bidirectional"))
      (node (ref "U$17") (pin "VS+") (pinfunction "VS+_VS+") (pintype "bidirectional"))
      (node (ref "U$9") (pin "1") (pinfunction "1_1") (pintype "bidirectional"))
    )
    (net (code "41") (name "SUPPLY2_+21V") (class "Default")
      (node (ref "5V_IN_CAP_1") (pin "2") (pinfunction "2_2") (pintype "bidirectional"))
      (node (ref "5V_IN_CAP_2") (pin "2") (pinfunction "2_2") (pintype "bidirectional"))
      (node (ref "5V_IN_CAP_3") (pin "2") (pinfunction "2_2") (pintype "bidirectional"))
      (node (ref "5V_IN_CAP_4") (pin "2") (pinfunction "2_2") (pintype "bidirectional"))
      (node (ref "BATTERY_VOLTAGE_DIVIDER_HIGH") (pin "P$2") (pinfunction "P$2_P$2") (pintype "bidirectional"))
      (node (ref "DC2DC_PROCESSOR_") (pin "VIN") (pinfunction "VIN_VIN") (pintype "bidirectional"))
      (node (ref "HIGH-SIDE_SWITCH") (pin "5") (pinfunction "OUT_5") (pintype "bidirectional"))
      (node (ref "MOTOR_IN.1UF") (pin "2") (pinfunction "2_2") (pintype "bidirectional"))
      (node (ref "MOTOR_IN.1UF1") (pin "2") (pinfunction "2_2") (pintype "bidirectional"))
      (node (ref "MOTOR_IN.1UF4") (pin "2") (pinfunction "2_2") (pintype "bidirectional"))
      (node (ref "MOTOR_IN10UF") (pin "2") (pinfunction "2_2") (pintype "bidirectional"))
      (node (ref "MOTOR_PULLUP") (pin "P$3") (pinfunction "P$3_P$3") (pintype "bidirectional"))
      (node (ref "PROCESSOR_PULLUP") (pin "P$3") (pinfunction "P$3_P$3") (pintype "bidirectional"))
      (node (ref "PROC_IN10UF") (pin "2") (pinfunction "2_2") (pintype "bidirectional"))
      (node (ref "PROC_IN_.1UF") (pin "2") (pinfunction "2_2") (pintype "bidirectional"))
      (node (ref "PROC_IN_.1UF1") (pin "2") (pinfunction "2_2") (pintype "bidirectional"))
      (node (ref "PROC_IN_.1UF2") (pin "2") (pinfunction "2_2") (pintype "bidirectional"))
      (node (ref "U$17") (pin "VIN") (pinfunction "VIN_VIN") (pintype "bidirectional"))
      (node (ref "U$4") (pin "VIN") (pinfunction "VIN_VIN") (pintype "bidirectional"))
    )
    (net (code "42") (name "unconnected-(HIGH-SIDE_SWITCH-ST-Pad4)") (class "Default")
      (node (ref "HIGH-SIDE_SWITCH") (pin "4") (pinfunction "ST_4") (pintype "bidirectional"))
    )
    (net (code "43") (name "unconnected-(U$14-3V3-PadP$29)") (class "Default")
      (node (ref "U$14") (pin "P$29") (pinfunction "3V3_P$29") (pintype "bidirectional"))
    )
    (net (code "44") (name "unconnected-(U$14-D13-PadP$30)") (class "Default")
      (node (ref "U$14") (pin "P$30") (pinfunction "D13_P$30") (pintype "bidirectional"))
    )
    (net (code "45") (name "unconnected-(U$14-REF-PadP$28)") (class "Default")
      (node (ref "U$14") (pin "P$28") (pinfunction "REF_P$28") (pintype "bidirectional"))
    )
    (net (code "46") (name "unconnected-(U$14-RST1-PadP$13)") (class "Default")
      (node (ref "U$14") (pin "P$13") (pinfunction "RST1_P$13") (pintype "bidirectional"))
    )
    (net (code "47") (name "unconnected-(U$14-RST2-PadP$18)") (class "Default")
      (node (ref "U$14") (pin "P$18") (pinfunction "RST2_P$18") (pintype "bidirectional"))
    )
    (net (code "48") (name "unconnected-(U$14-VIN-PadP$16)") (class "Default")
      (node (ref "U$14") (pin "P$16") (pinfunction "VIN_P$16") (pintype "bidirectional"))
    )
  )
)
